# Tiny817_Xplained_Pro_EDBG.net
KiCad netlist of a schematic drawn in Altium Designer
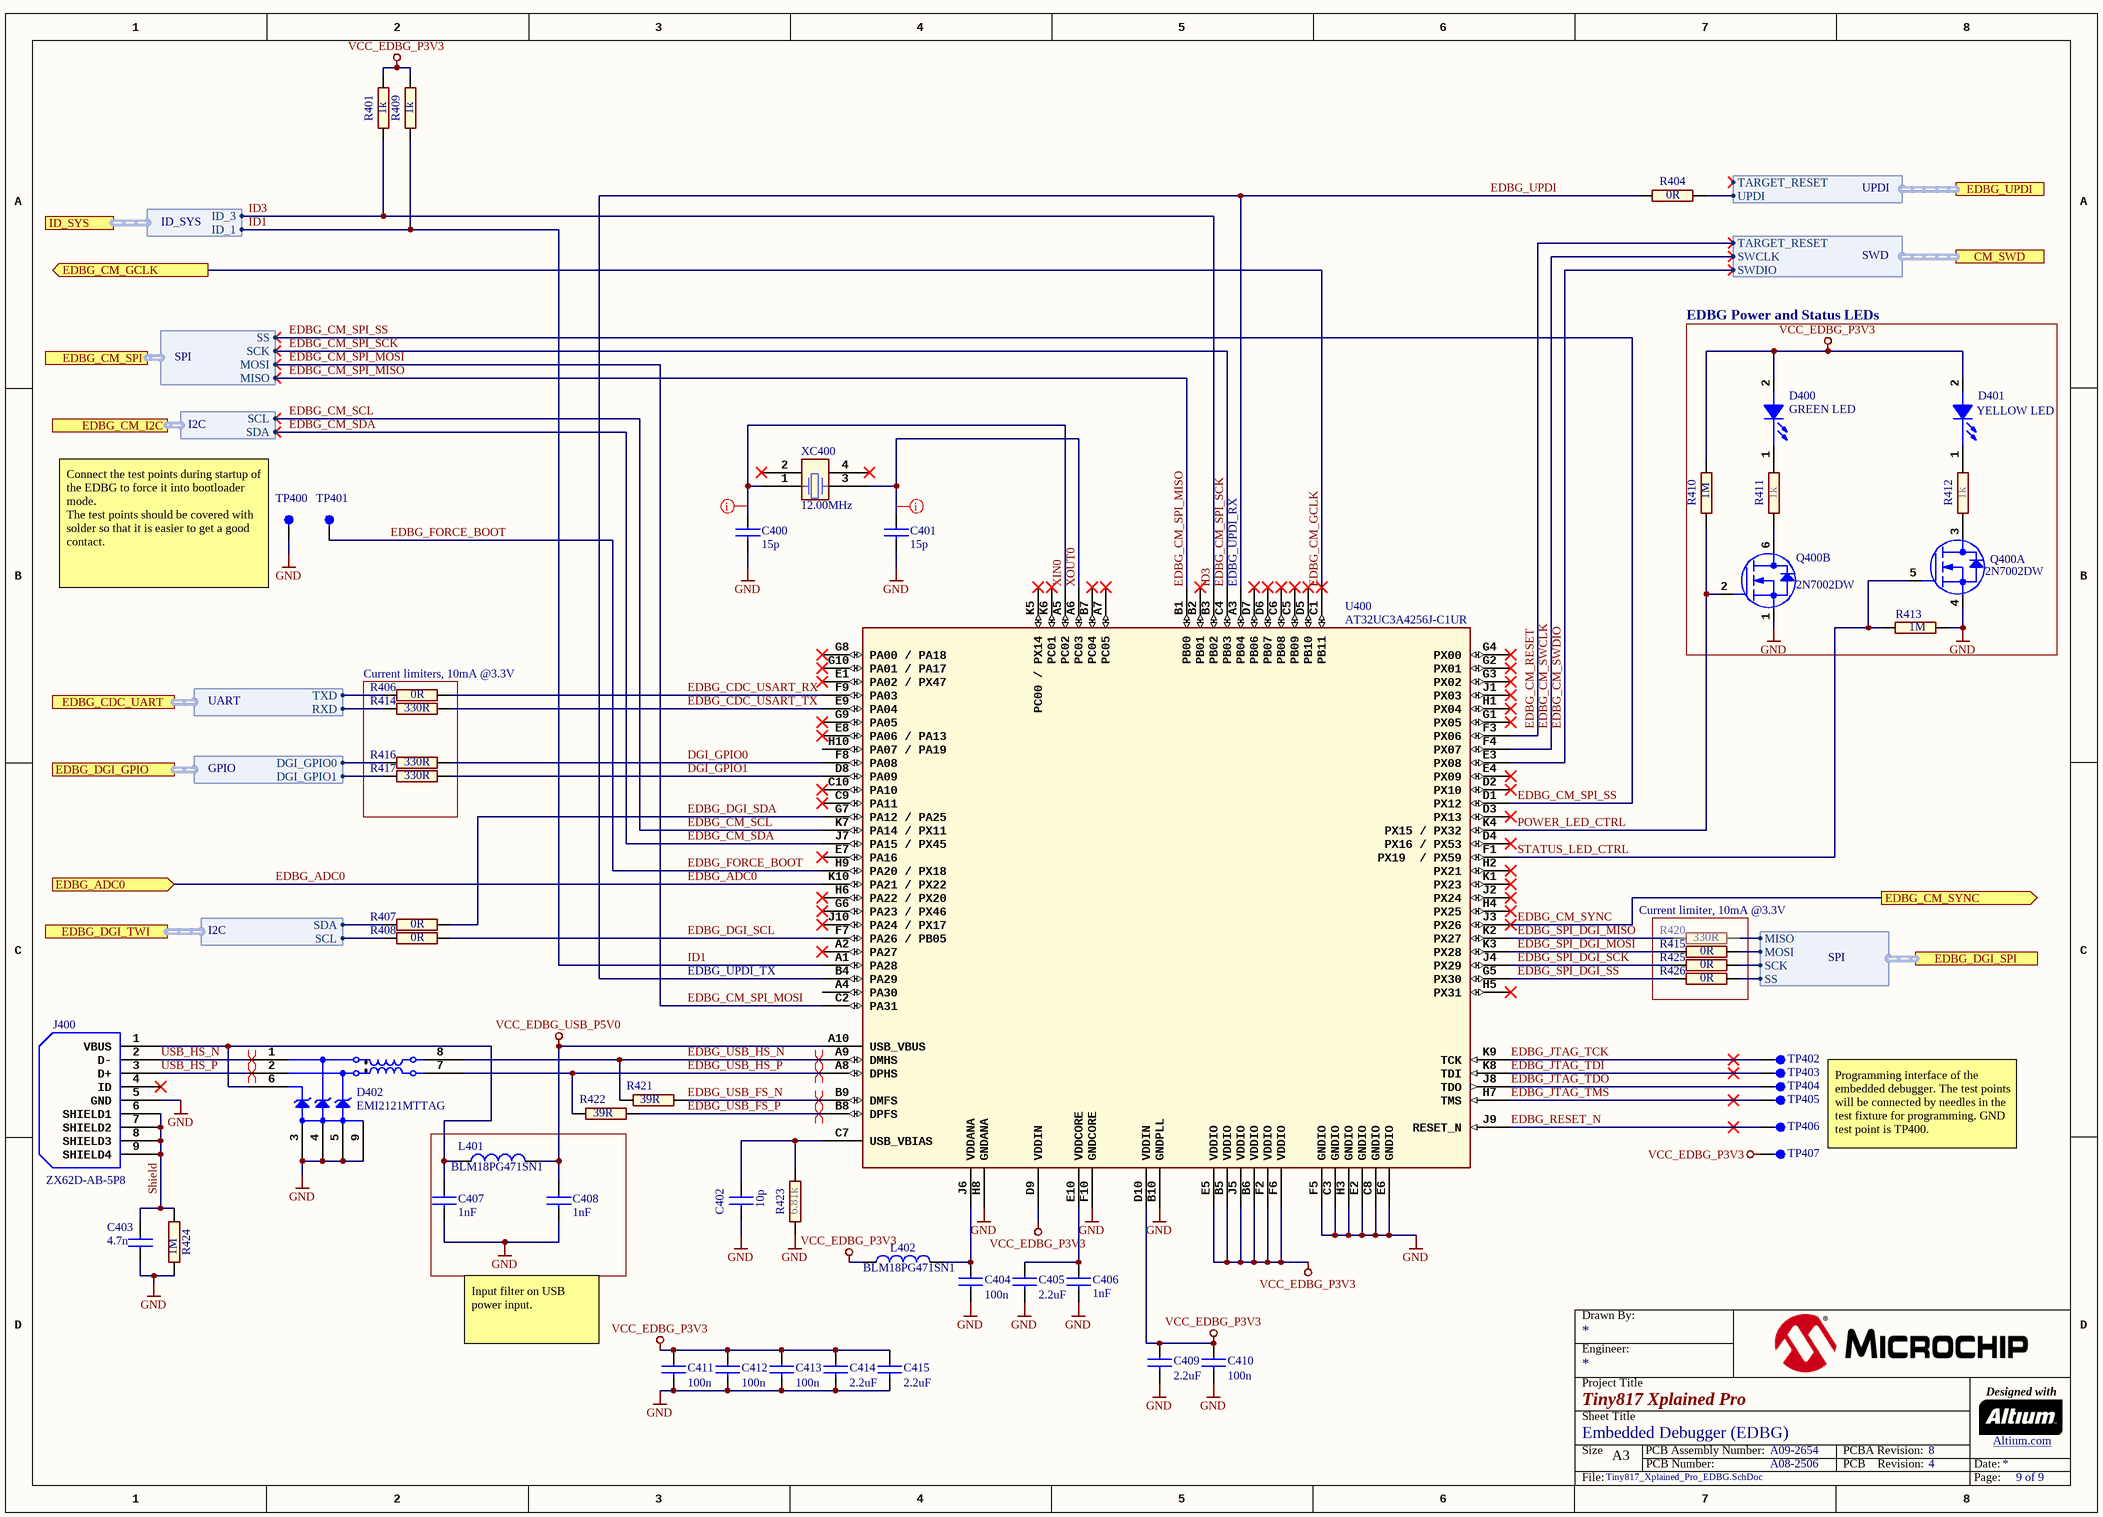
[diagram p0: Tiny817_Xplained_Pro_EDBG.SchDoc]

(export (version "E")
  (design (tool "Eeschema 10.0.6"))
  (components
    (comp (ref "C400")
      (value "15p")
      (footprint "AP1-00053")
      (description "Ceramic capacitor, SMD 0402, NP0, 50V, +/-5%")
      (fields (field (name "TOLERANCE") "50V, +/-5%") (field (name "MANUFACTURER") "AVX"))
      (libsource (lib "AltiumDbLib") (part "CAP-NONPOL"))
    )
    (comp (ref "C401")
      (value "15p")
      (footprint "AP1-00053")
      (description "Ceramic capacitor, SMD 0402, NP0, 50V, +/-5%")
      (fields (field (name "TOLERANCE") "50V, +/-5%") (field (name "MANUFACTURER") "AVX"))
      (libsource (lib "AltiumDbLib") (part "CAP-NONPOL"))
    )
    (comp (ref "C402")
      (value "10p")
      (footprint "AP1-00053")
      (description "Ceramic capacitor, SMD 0402, NP0, 50V, +/-5%")
      (fields (field (name "TOLERANCE") "50V, +/-5%") (field (name "MANUFACTURER") "AVX"))
      (libsource (lib "AltiumDbLib") (part "CAP-NONPOL"))
    )
    (comp (ref "C403")
      (value "4.7n")
      (footprint "AP1-00053")
      (description "Ceramic capacitor, SMD 0402, X7R, 25V, +/-10% (de35287)")
      (fields (field (name "TOLERANCE") "25V, +/-10%") (field (name "MANUFACTURER") "PHYCOMP"))
      (libsource (lib "AltiumDbLib") (part "CAP-NONPOL"))
    )
    (comp (ref "C404")
      (value "100n")
      (footprint "AP1-00053")
      (description "Ceramic capacitor, SMD 0402, X7R, 16V, +/-10%")
      (fields (field (name "TOLERANCE") "16V, +/-10%") (field (name "MANUFACTURER") "Kemet"))
      (libsource (lib "AltiumDbLib") (part "CAP-NONPOL"))
    )
    (comp (ref "C405")
      (value "2.2uF")
      (footprint "AP1-00053")
      (description "Ceramic capacitor, SMD 0402, X5R, 6.3V, +/-20%")
      (fields (field (name "TOLERANCE") "Â±20%") (field (name "MANUFACTURER") "Kemet"))
      (libsource (lib "AltiumDbLib") (part "CAP-NONPOL"))
    )
    (comp (ref "C406")
      (value "1nF")
      (footprint "AP1-00053")
      (description "Ceramic capacitor, SMD 0402, C0G, 50V, +/-5%")
      (fields (field (name "TOLERANCE") "5%") (field (name "MANUFACTURER") "Murata"))
      (libsource (lib "AltiumDbLib") (part "CAP-NONPOL"))
    )
    (comp (ref "C407")
      (value "1nF")
      (footprint "AP1-00053")
      (description "Ceramic capacitor, SMD 0402, C0G, 50V, +/-5%")
      (fields (field (name "TOLERANCE") "5%") (field (name "MANUFACTURER") "Murata"))
      (libsource (lib "AltiumDbLib") (part "CAP-NONPOL"))
    )
    (comp (ref "C408")
      (value "1nF")
      (footprint "AP1-00053")
      (description "Ceramic capacitor, SMD 0402, C0G, 50V, +/-5%")
      (fields (field (name "TOLERANCE") "5%") (field (name "MANUFACTURER") "Murata"))
      (libsource (lib "AltiumDbLib") (part "CAP-NONPOL"))
    )
    (comp (ref "C409")
      (value "2.2uF")
      (footprint "AP1-00053")
      (description "Ceramic capacitor, SMD 0402, X5R, 6.3V, +/-20%")
      (fields (field (name "TOLERANCE") "Â±20%") (field (name "MANUFACTURER") "Kemet"))
      (libsource (lib "AltiumDbLib") (part "CAP-NONPOL"))
    )
    (comp (ref "C410")
      (value "100n")
      (footprint "AP1-00053")
      (description "Ceramic capacitor, SMD 0402, X7R, 16V, +/-10%")
      (fields (field (name "TOLERANCE") "16V, +/-10%") (field (name "MANUFACTURER") "Kemet"))
      (libsource (lib "AltiumDbLib") (part "CAP-NONPOL"))
    )
    (comp (ref "C411")
      (value "100n")
      (footprint "AP1-00053")
      (description "Ceramic capacitor, SMD 0402, X7R, 16V, +/-10%")
      (fields (field (name "TOLERANCE") "16V, +/-10%") (field (name "MANUFACTURER") "Kemet"))
      (libsource (lib "AltiumDbLib") (part "CAP-NONPOL"))
    )
    (comp (ref "C412")
      (value "100n")
      (footprint "AP1-00053")
      (description "Ceramic capacitor, SMD 0402, X7R, 16V, +/-10%")
      (fields (field (name "TOLERANCE") "16V, +/-10%") (field (name "MANUFACTURER") "Kemet"))
      (libsource (lib "AltiumDbLib") (part "CAP-NONPOL"))
    )
    (comp (ref "C413")
      (value "100n")
      (footprint "AP1-00053")
      (description "Ceramic capacitor, SMD 0402, X7R, 16V, +/-10%")
      (fields (field (name "TOLERANCE") "16V, +/-10%") (field (name "MANUFACTURER") "Kemet"))
      (libsource (lib "AltiumDbLib") (part "CAP-NONPOL"))
    )
    (comp (ref "C414")
      (value "2.2uF")
      (footprint "AP1-00053")
      (description "Ceramic capacitor, SMD 0402, X5R, 6.3V, +/-20%")
      (fields (field (name "TOLERANCE") "Â±20%") (field (name "MANUFACTURER") "Kemet"))
      (libsource (lib "AltiumDbLib") (part "CAP-NONPOL"))
    )
    (comp (ref "C415")
      (value "2.2uF")
      (footprint "AP1-00053")
      (description "Ceramic capacitor, SMD 0402, X5R, 6.3V, +/-20%")
      (fields (field (name "TOLERANCE") "Â±20%") (field (name "MANUFACTURER") "Kemet"))
      (libsource (lib "AltiumDbLib") (part "CAP-NONPOL"))
    )
    (comp (ref "D400")
      (value "GREEN LED")
      (footprint "AP4-00160")
      (description "LED, SMD 0402, Green, Wave length=569nm, 2.1mcd @ (1mA, 1.9Vf)rohm")
      (fields (field (name "MANUFACTURER") "ROHM") (field (name "MPN") "SML-P12MTT86R"))
      (libsource (lib "AltiumDbLib") (part "LED_12"))
    )
    (comp (ref "D401")
      (value "YELLOW LED")
      (footprint "AP4-00160")
      (description "LED, SMD 0402, Yellow, Wave length=586nm, 7.6mcd @ (1mA, 1.9Vf)")
      (fields (field (name "MANUFACTURER") "ROHM") (field (name "MPN") "SML-P12YTT86R"))
      (libsource (lib "AltiumDbLib") (part "LED_12"))
    )
    (comp (ref "D402")
      (value "EMI2121MTTAG")
      (footprint "AP4-00159")
      (description "EMI2121, SZEMI2121 Single Pair Common Mode Filter with ESD Protection")
      (fields (field (name "MANUFACTURER") "ON Semiconductor"))
      (libsource (lib "AltiumDbLib") (part "EMI2121"))
    )
    (comp (ref "J400")
      (value "ZX62D-AB-5P8")
      (footprint "AP8-00852")
      (description "Micro USB AB Connector, Standard SMT + DIP")
      (fields (field (name "MANUFACTURER") "Hirose") (field (name "MPN") "ZX62D-AB-5P8(30)"))
      (libsource (lib "AltiumDbLib") (part "USB_AB"))
    )
    (comp (ref "L401")
      (value "BLM18PG471SN1")
      (footprint "AP3-00005")
      (description "SMD RF inductor 0603. Z=470Ohm (@100MHz), Max R(dc)=0.20Ohm, Max current=1A")
      (fields (field (name "MANUFACTURER") "Murata"))
      (libsource (lib "AltiumDbLib") (part "INDUCTOR"))
    )
    (comp (ref "L402")
      (value "BLM18PG471SN1")
      (footprint "AP3-00005")
      (description "SMD RF inductor 0603. Z=470Ohm (@100MHz), Max R(dc)=0.20Ohm, Max current=1A")
      (fields (field (name "MANUFACTURER") "Murata"))
      (libsource (lib "AltiumDbLib") (part "INDUCTOR"))
    )
    (comp (ref "Q400")
      (value "2N7002DW")
      (footprint "AP5-00001")
      (description "Dual N-Channel MOSFET, 60V, 115mA cont,RDS(ON) < 7.5 Ohm @50mA@5V, SOT-363")
      (fields
        (field (name "MANUFACTURER") "Fairchild")
        (field (name "Comment") "Same as 2N7002 but with two MOSFETs in one package")
      )
      (libsource (lib "AltiumDbLib") (part "MOSFET_DUAL_N_S2G2D1S1G1D2"))
    )
    (comp (ref "R401")
      (value "1k")
      (footprint "AP2-00000")
      (description "Thick film resistor, SMD 0402, 1/16W, 1%")
      (fields (field (name "TOLERANCE") "1 %") (field (name "MANUFACTURER") "ASJ Holdings"))
      (libsource (lib "") (part "R2_4"))
    )
    (comp (ref "R404")
      (value "0R")
      (footprint "AP2-00000")
      (description "RES 0.0 OHM 1/16W 0402 SMD")
      (fields (field (name "TOLERANCE") "1 %") (field (name "MANUFACTURER") "(n/a)"))
      (libsource (lib "") (part "R2_3"))
    )
    (comp (ref "R406")
      (value "0R")
      (footprint "AP2-00000")
      (description "RES 0.0 OHM 1/16W 0402 SMD")
      (fields (field (name "TOLERANCE") "1 %") (field (name "MANUFACTURER") "(n/a)"))
      (libsource (lib "") (part "R2_3"))
    )
    (comp (ref "R407")
      (value "0R")
      (footprint "AP2-00000")
      (description "RES 0.0 OHM 1/16W 0402 SMD")
      (fields (field (name "TOLERANCE") "1 %") (field (name "MANUFACTURER") "(n/a)"))
      (libsource (lib "") (part "R2_3"))
    )
    (comp (ref "R408")
      (value "0R")
      (footprint "AP2-00000")
      (description "RES 0.0 OHM 1/16W 0402 SMD")
      (fields (field (name "TOLERANCE") "1 %") (field (name "MANUFACTURER") "(n/a)"))
      (libsource (lib "") (part "R2_3"))
    )
    (comp (ref "R409")
      (value "1k")
      (footprint "AP2-00000")
      (description "Thick film resistor, SMD 0402, 1/16W, 1%")
      (fields (field (name "TOLERANCE") "1 %") (field (name "MANUFACTURER") "ASJ Holdings"))
      (libsource (lib "") (part "R2_4"))
    )
    (comp (ref "R410")
      (value "1M")
      (footprint "AP2-00011")
      (description "Thick film resistor, SMD 0402, 1/16W, 1%")
      (fields (field (name "TOLERANCE") "1 %") (field (name "MANUFACTURER") "ASJ Holdings"))
      (libsource (lib "") (part "R2_4"))
    )
    (comp (ref "R411")
      (value "1k")
      (footprint "AP2-00011")
      (description "Thick film resistor, SMD 0402, 1/16W, 1%")
      (fields (field (name "TOLERANCE") "1 %") (field (name "MANUFACTURER") "ASJ Holdings"))
      (libsource (lib "") (part "R2_4"))
    )
    (comp (ref "R412")
      (value "1k")
      (footprint "AP2-00011")
      (description "Thick film resistor, SMD 0402, 1/16W, 1%")
      (fields (field (name "TOLERANCE") "1 %") (field (name "MANUFACTURER") "ASJ Holdings"))
      (libsource (lib "") (part "R2_4"))
    )
    (comp (ref "R413")
      (value "1M")
      (footprint "AP2-00011")
      (description "Thick film resistor, SMD 0402, 1/16W, 1%")
      (fields (field (name "TOLERANCE") "1 %") (field (name "MANUFACTURER") "ASJ Holdings"))
      (libsource (lib "") (part "R2_3"))
    )
    (comp (ref "R414")
      (value "330R")
      (footprint "AP2-00000")
      (description "Thick film resistor, SMD 0402, 1/16W, 1%")
      (fields (field (name "TOLERANCE") "1 %") (field (name "MANUFACTURER") "ASJ Holdings"))
      (libsource (lib "AltiumDbLib") (part "R2"))
    )
    (comp (ref "R415")
      (value "0R")
      (footprint "AP2-00000")
      (description "RES 0.0 OHM 1/16W 0402 SMD")
      (fields (field (name "TOLERANCE") "1 %") (field (name "MANUFACTURER") "(n/a)"))
      (libsource (lib "") (part "R2_3"))
    )
    (comp (ref "R416")
      (value "330R")
      (footprint "AP2-00000")
      (description "Thick film resistor, SMD 0402, 1/16W, 1%")
      (fields (field (name "TOLERANCE") "1 %") (field (name "MANUFACTURER") "ASJ Holdings"))
      (libsource (lib "AltiumDbLib") (part "R2"))
    )
    (comp (ref "R417")
      (value "330R")
      (footprint "AP2-00000")
      (description "Thick film resistor, SMD 0402, 1/16W, 1%")
      (fields (field (name "TOLERANCE") "1 %") (field (name "MANUFACTURER") "ASJ Holdings"))
      (libsource (lib "AltiumDbLib") (part "R2"))
    )
    (comp (ref "R420")
      (value "330R")
      (footprint "AP2-00000")
      (description "Thick film resistor, SMD 0402, 1/16W, 1%")
      (fields (field (name "TOLERANCE") "1 %") (field (name "MANUFACTURER") "ASJ Holdings"))
      (libsource (lib "AltiumDbLib") (part "R2"))
    )
    (comp (ref "R421")
      (value "39R")
      (footprint "AP2-00011")
      (description "Thick film resistor, SMD 0402, 1/16W, 1%")
      (fields (field (name "TOLERANCE") "1 %") (field (name "MANUFACTURER") "ASJ Holdings"))
      (libsource (lib "") (part "R2_1"))
    )
    (comp (ref "R422")
      (value "39R")
      (footprint "AP2-00011")
      (description "Thick film resistor, SMD 0402, 1/16W, 1%")
      (fields (field (name "TOLERANCE") "1 %") (field (name "MANUFACTURER") "ASJ Holdings"))
      (libsource (lib "") (part "R2_1"))
    )
    (comp (ref "R423")
      (value "6.81k")
      (footprint "AP2-00011")
      (description "Thick film resistor, SMD 0402, 1/16W, 1%")
      (fields (field (name "TOLERANCE") "1%") (field (name "MANUFACTURER") "Vishay"))
      (libsource (lib "") (part "R2_4"))
    )
    (comp (ref "R424")
      (value "1M")
      (footprint "AP2-00011")
      (description "Thick film resistor, SMD 0402, 1/16W, 1%")
      (fields (field (name "TOLERANCE") "1 %") (field (name "MANUFACTURER") "ASJ Holdings"))
      (libsource (lib "") (part "R2_2"))
    )
    (comp (ref "R425")
      (value "0R")
      (footprint "AP2-00000")
      (description "RES 0.0 OHM 1/16W 0402 SMD")
      (fields (field (name "TOLERANCE") "1 %") (field (name "MANUFACTURER") "(n/a)"))
      (libsource (lib "") (part "R2_3"))
    )
    (comp (ref "R426")
      (value "0R")
      (footprint "AP2-00000")
      (description "RES 0.0 OHM 1/16W 0402 SMD")
      (fields (field (name "TOLERANCE") "1 %") (field (name "MANUFACTURER") "(n/a)"))
      (libsource (lib "") (part "R2_3"))
    )
    (comp (ref "TP400")
      (value "~")
      (footprint "AP8-00010")
      (description "Single SMD testpad")
      (libsource (lib "AltiumDbLib") (part "TESTPOINT"))
    )
    (comp (ref "TP401")
      (value "~")
      (footprint "AP8-00010")
      (description "Single SMD testpad")
      (libsource (lib "AltiumDbLib") (part "TESTPOINT"))
    )
    (comp (ref "TP402")
      (value "~")
      (footprint "AP8-00010")
      (description "Single SMD testpad")
      (libsource (lib "AltiumDbLib") (part "TESTPOINT"))
    )
    (comp (ref "TP403")
      (value "~")
      (footprint "AP8-00010")
      (description "Single SMD testpad")
      (libsource (lib "AltiumDbLib") (part "TESTPOINT"))
    )
    (comp (ref "TP404")
      (value "~")
      (footprint "AP8-00010")
      (description "Single SMD testpad")
      (libsource (lib "AltiumDbLib") (part "TESTPOINT"))
    )
    (comp (ref "TP405")
      (value "~")
      (footprint "AP8-00010")
      (description "Single SMD testpad")
      (libsource (lib "AltiumDbLib") (part "TESTPOINT"))
    )
    (comp (ref "TP406")
      (value "~")
      (footprint "AP8-00010")
      (description "Single SMD testpad")
      (libsource (lib "AltiumDbLib") (part "TESTPOINT"))
    )
    (comp (ref "TP407")
      (value "~")
      (footprint "AP8-00010")
      (description "Single SMD testpad")
      (libsource (lib "AltiumDbLib") (part "TESTPOINT"))
    )
    (comp (ref "U400")
      (value "AT32UC3A4256J-C1UR")
      (footprint "AP6-00206")
      (description "EDBG controller")
      (fields (field (name "MANUFACTURER") "Microchip") (field (name "Comment") "100 ball VFBGA"))
      (libsource (lib "AltiumDbLib") (part "AT32UC3A4_VFBGA"))
    )
    (comp (ref "XC400")
      (value "12.00MHz")
      (footprint "AP7-00089")
      (description "Kyocera CX3225GB12000H0KPSC1, 12MHz, 12pF, SMD crystal")
      (fields
        (field (name "TOLERANCE") "Â±30ppm")
        (field (name "MANUFACTURER") "Kyocera Crystal Device Corporation")
      )
      (libsource (lib "AltiumDbLib") (part "CRYSTAL1324"))
    )
  )
  (nets
    (net (code "7") (name "/DGI_GPIO0") (class "Default")
      (node (ref "R416") (pin "2") (pinfunction "2_2") (pintype "passive"))
      (node (ref "U400") (pin "F8") (pinfunction "PA08_F8") (pintype "bidirectional"))
    )
    (net (code "8") (name "/DGI_GPIO1") (class "Default")
      (node (ref "R417") (pin "2") (pinfunction "2_2") (pintype "passive"))
      (node (ref "U400") (pin "D8") (pinfunction "PA09_D8") (pintype "bidirectional"))
    )
    (net (code "9") (name "/EDBG_ADC0") (class "Default")
      (node (ref "U400") (pin "K10") (pinfunction "PA21_/_PX22_K10") (pintype "bidirectional"))
    )
    (net (code "10") (name "/EDBG_CDC_USART_RX") (class "Default")
      (node (ref "R406") (pin "1") (pinfunction "1_1") (pintype "passive"))
      (node (ref "U400") (pin "F9") (pinfunction "PA03_F9") (pintype "bidirectional"))
    )
    (net (code "11") (name "/EDBG_CDC_USART_TX") (class "Default")
      (node (ref "R414") (pin "2") (pinfunction "2_2") (pintype "passive"))
      (node (ref "U400") (pin "E9") (pinfunction "PA04_E9") (pintype "bidirectional"))
    )
    (net (code "12") (name "/EDBG_CM_GCLK") (class "Default")
      (node (ref "U400") (pin "C1") (pinfunction "PB11_C1") (pintype "bidirectional+no_connect"))
    )
    (net (code "13") (name "/EDBG_CM_RESET") (class "Default")
      (node (ref "U400") (pin "F3") (pinfunction "PX06_F3") (pintype "bidirectional+no_connect"))
    )
    (net (code "14") (name "/EDBG_CM_SCL") (class "Default")
      (node (ref "U400") (pin "K7") (pinfunction "PA14_/_PX11_K7") (pintype "bidirectional+no_connect"))
    )
    (net (code "15") (name "/EDBG_CM_SDA") (class "Default")
      (node (ref "U400") (pin "J7") (pinfunction "PA15_/_PX45_J7") (pintype "bidirectional+no_connect"))
    )
    (net (code "16") (name "/EDBG_CM_SPI_MISO") (class "Default")
      (node (ref "U400") (pin "B1") (pinfunction "PB00_B1") (pintype "bidirectional+no_connect"))
    )
    (net (code "17") (name "/EDBG_CM_SPI_MOSI") (class "Default")
      (node (ref "U400") (pin "C2") (pinfunction "PA31_C2") (pintype "bidirectional+no_connect"))
    )
    (net (code "18") (name "/EDBG_CM_SPI_SCK") (class "Default")
      (node (ref "U400") (pin "C4") (pinfunction "PB03_C4") (pintype "bidirectional+no_connect"))
    )
    (net (code "19") (name "/EDBG_CM_SPI_SS") (class "Default")
      (node (ref "U400") (pin "D1") (pinfunction "PX12_D1") (pintype "bidirectional+no_connect"))
    )
    (net (code "20") (name "/EDBG_CM_SWCLK") (class "Default")
      (node (ref "U400") (pin "F4") (pinfunction "PX07_F4") (pintype "bidirectional+no_connect"))
    )
    (net (code "21") (name "/EDBG_CM_SWDIO") (class "Default")
      (node (ref "U400") (pin "E3") (pinfunction "PX08_E3") (pintype "bidirectional+no_connect"))
    )
    (net (code "22") (name "/EDBG_CM_SYNC") (class "Default")
      (node (ref "U400") (pin "J3") (pinfunction "PX26_J3") (pintype "bidirectional+no_connect"))
    )
    (net (code "23") (name "/EDBG_DGI_SCL") (class "Default")
      (node (ref "R408") (pin "1") (pinfunction "1_1") (pintype "passive"))
      (node (ref "U400") (pin "F7") (pinfunction "PA26_/_PB05_F7") (pintype "bidirectional"))
    )
    (net (code "24") (name "/EDBG_DGI_SDA") (class "Default")
      (node (ref "R407") (pin "1") (pinfunction "1_1") (pintype "passive"))
      (node (ref "U400") (pin "G7") (pinfunction "PA12_/_PA25_G7") (pintype "bidirectional"))
    )
    (net (code "25") (name "/EDBG_FORCE_BOOT") (class "Default")
      (node (ref "TP401") (pin "1") (pinfunction "1_1") (pintype "passive"))
      (node (ref "U400") (pin "H9") (pinfunction "PA20_/_PX18_H9") (pintype "bidirectional"))
    )
    (net (code "26") (name "/EDBG_JTAG_TCK") (class "Default")
      (node (ref "TP402") (pin "1") (pinfunction "1_1") (pintype "passive"))
      (node (ref "U400") (pin "K9") (pinfunction "TCK_K9") (pintype "input"))
    )
    (net (code "27") (name "/EDBG_JTAG_TDI") (class "Default")
      (node (ref "TP403") (pin "1") (pinfunction "1_1") (pintype "passive"))
      (node (ref "U400") (pin "K8") (pinfunction "TDI_K8") (pintype "input"))
    )
    (net (code "28") (name "/EDBG_JTAG_TDO") (class "Default")
      (node (ref "TP404") (pin "1") (pinfunction "1_1") (pintype "passive"))
      (node (ref "U400") (pin "J8") (pinfunction "TDO_J8") (pintype "output"))
    )
    (net (code "29") (name "/EDBG_JTAG_TMS") (class "Default")
      (node (ref "TP405") (pin "1") (pinfunction "1_1") (pintype "passive"))
      (node (ref "U400") (pin "H7") (pinfunction "TMS_H7") (pintype "input"))
    )
    (net (code "30") (name "/EDBG_RESET_N") (class "Default")
      (node (ref "TP406") (pin "1") (pinfunction "1_1") (pintype "passive"))
      (node (ref "U400") (pin "J9") (pinfunction "RESET_N_J9") (pintype "input"))
    )
    (net (code "31") (name "/EDBG_SPI_DGI_MISO") (class "Default")
      (node (ref "R420") (pin "1") (pinfunction "1_1") (pintype "passive"))
      (node (ref "U400") (pin "K2") (pinfunction "PX27_K2") (pintype "bidirectional"))
    )
    (net (code "32") (name "/EDBG_SPI_DGI_MOSI") (class "Default")
      (node (ref "R415") (pin "2") (pinfunction "2_2") (pintype "passive"))
      (node (ref "U400") (pin "K3") (pinfunction "PX28_K3") (pintype "bidirectional"))
    )
    (net (code "33") (name "/EDBG_SPI_DGI_SCK") (class "Default")
      (node (ref "R425") (pin "2") (pinfunction "2_2") (pintype "passive"))
      (node (ref "U400") (pin "J4") (pinfunction "PX29_J4") (pintype "bidirectional"))
    )
    (net (code "34") (name "/EDBG_SPI_DGI_SS") (class "Default")
      (node (ref "R426") (pin "2") (pinfunction "2_2") (pintype "passive"))
      (node (ref "U400") (pin "G5") (pinfunction "PX30_G5") (pintype "bidirectional"))
    )
    (net (code "35") (name "/EDBG_UPDI") (class "Default")
      (node (ref "R404") (pin "2") (pinfunction "2_2") (pintype "passive"))
      (node (ref "U400") (pin "A3") (pinfunction "PB04_A3") (pintype "bidirectional"))
      (node (ref "U400") (pin "B4") (pinfunction "PA29_B4") (pintype "bidirectional"))
    )
    (net (code "36") (name "/EDBG_USB_FS_N") (class "Default")
      (node (ref "R421") (pin "2") (pinfunction "2_2") (pintype "passive"))
      (node (ref "U400") (pin "B9") (pinfunction "DMFS_B9") (pintype "bidirectional"))
    )
    (net (code "37") (name "/EDBG_USB_FS_P") (class "Default")
      (node (ref "R422") (pin "2") (pinfunction "2_2") (pintype "passive"))
      (node (ref "U400") (pin "B8") (pinfunction "DPFS_B8") (pintype "bidirectional"))
    )
    (net (code "38") (name "/EDBG_USB_HS_N") (class "Default")
      (node (ref "D402") (pin "8") (pinfunction "DIFF1_INT_8") (pintype "passive"))
      (node (ref "R421") (pin "1") (pinfunction "1_1") (pintype "passive"))
      (node (ref "U400") (pin "A9") (pinfunction "DMHS_A9") (pintype "bidirectional"))
    )
    (net (code "39") (name "/EDBG_USB_HS_P") (class "Default")
      (node (ref "D402") (pin "7") (pinfunction "DIFF2_INT_7") (pintype "passive"))
      (node (ref "R422") (pin "1") (pinfunction "1_1") (pintype "passive"))
      (node (ref "U400") (pin "A8") (pinfunction "DPHS_A8") (pintype "bidirectional"))
    )
    (net (code "40") (name "/ID1") (class "Default")
      (node (ref "R409") (pin "1") (pinfunction "1_1") (pintype "passive"))
      (node (ref "U400") (pin "A1") (pinfunction "PA28_A1") (pintype "bidirectional"))
    )
    (net (code "41") (name "/ID3") (class "Default")
      (node (ref "R401") (pin "1") (pinfunction "1_1") (pintype "passive"))
      (node (ref "U400") (pin "B3") (pinfunction "PB02_B3") (pintype "bidirectional"))
    )
    (net (code "42") (name "/POWER_LED_CTRL") (class "Default")
      (node (ref "Q400") (pin "2") (pinfunction "G2_2") (pintype "passive"))
      (node (ref "R410") (pin "1") (pinfunction "1_1") (pintype "passive"))
      (node (ref "U400") (pin "K4") (pinfunction "PX15_/_PX32_K4") (pintype "bidirectional"))
    )
    (net (code "43") (name "/RXD") (class "Default")
      (node (ref "R414") (pin "1") (pinfunction "1_1") (pintype "passive"))
    )
    (net (code "44") (name "/STATUS_LED_CTRL") (class "Default")
      (node (ref "Q400") (pin "5") (pinfunction "G1_5") (pintype "passive"))
      (node (ref "R413") (pin "2") (pinfunction "2_2") (pintype "passive"))
      (node (ref "U400") (pin "F1") (pinfunction "PX19__/_PX59_F1") (pintype "bidirectional"))
    )
    (net (code "45") (name "/Shield") (class "Default")
      (node (ref "C403") (pin "2") (pinfunction "2_2") (pintype "passive"))
      (node (ref "J400") (pin "6") (pinfunction "SHIELD1_6") (pintype "passive"))
      (node (ref "J400") (pin "7") (pinfunction "SHIELD2_7") (pintype "passive"))
      (node (ref "J400") (pin "8") (pinfunction "SHIELD3_8") (pintype "passive"))
      (node (ref "J400") (pin "9") (pinfunction "SHIELD4_9") (pintype "passive"))
      (node (ref "R424") (pin "2") (pinfunction "2_2") (pintype "passive"))
    )
    (net (code "46") (name "/TXD") (class "Default")
      (node (ref "R406") (pin "2") (pinfunction "2_2") (pintype "passive"))
    )
    (net (code "47") (name "/UPDI") (class "Default")
      (node (ref "R404") (pin "1") (pinfunction "1_1") (pintype "passive"))
    )
    (net (code "48") (name "/USB_HS_N") (class "Default")
      (node (ref "D402") (pin "1") (pinfunction "DIFF1_EXT_1") (pintype "passive"))
      (node (ref "J400") (pin "2") (pinfunction "D-_2") (pintype "passive"))
    )
    (net (code "49") (name "/USB_HS_P") (class "Default")
      (node (ref "D402") (pin "2") (pinfunction "DIFF2_EXT_2") (pintype "passive"))
      (node (ref "J400") (pin "3") (pinfunction "D+_3") (pintype "passive"))
    )
    (net (code "50") (name "/XIN0") (class "Default")
      (node (ref "C400") (pin "1") (pinfunction "1_1") (pintype "passive"))
      (node (ref "U400") (pin "A5") (pinfunction "PC02_A5") (pintype "bidirectional"))
      (node (ref "XC400") (pin "1") (pinfunction "1_1") (pintype "passive"))
    )
    (net (code "51") (name "/XOUT0") (class "Default")
      (node (ref "C401") (pin "1") (pinfunction "1_1") (pintype "passive"))
      (node (ref "U400") (pin "A6") (pinfunction "PC03_A6") (pintype "bidirectional"))
      (node (ref "XC400") (pin "3") (pinfunction "3_3") (pintype "passive"))
    )
    (net (code "59") (name "GND") (class "Default")
      (node (ref "C400") (pin "2") (pinfunction "2_2") (pintype "passive"))
      (node (ref "C401") (pin "2") (pinfunction "2_2") (pintype "passive"))
      (node (ref "C402") (pin "2") (pinfunction "2_2") (pintype "passive"))
      (node (ref "C403") (pin "1") (pinfunction "1_1") (pintype "passive"))
      (node (ref "C404") (pin "2") (pinfunction "2_2") (pintype "passive"))
      (node (ref "C405") (pin "2") (pinfunction "2_2") (pintype "passive"))
      (node (ref "C406") (pin "2") (pinfunction "2_2") (pintype "passive"))
      (node (ref "C407") (pin "2") (pinfunction "2_2") (pintype "passive"))
      (node (ref "C408") (pin "2") (pinfunction "2_2") (pintype "passive"))
      (node (ref "C409") (pin "2") (pinfunction "2_2") (pintype "passive"))
      (node (ref "C410") (pin "2") (pinfunction "2_2") (pintype "passive"))
      (node (ref "C411") (pin "2") (pinfunction "2_2") (pintype "passive"))
      (node (ref "C412") (pin "2") (pinfunction "2_2") (pintype "passive"))
      (node (ref "C413") (pin "2") (pinfunction "2_2") (pintype "passive"))
      (node (ref "C414") (pin "2") (pinfunction "2_2") (pintype "passive"))
      (node (ref "C415") (pin "2") (pinfunction "2_2") (pintype "passive"))
      (node (ref "D402") (pin "3") (pinfunction "GND_3") (pintype "power_in"))
      (node (ref "D402") (pin "4") (pinfunction "GND_4") (pintype "power_in"))
      (node (ref "D402") (pin "5") (pinfunction "GND_5") (pintype "power_in"))
      (node (ref "D402") (pin "9") (pinfunction "GND_9") (pintype "power_in"))
      (node (ref "J400") (pin "5") (pinfunction "GND_5") (pintype "passive"))
      (node (ref "Q400") (pin "1") (pinfunction "S2_1") (pintype "passive"))
      (node (ref "Q400") (pin "4") (pinfunction "S1_4") (pintype "passive"))
      (node (ref "R413") (pin "1") (pinfunction "1_1") (pintype "passive"))
      (node (ref "R423") (pin "1") (pinfunction "1_1") (pintype "passive"))
      (node (ref "R424") (pin "1") (pinfunction "1_1") (pintype "passive"))
      (node (ref "TP400") (pin "1") (pinfunction "1_1") (pintype "passive"))
      (node (ref "U400") (pin "B10") (pinfunction "GNDPLL_B10") (pintype "power_in"))
      (node (ref "U400") (pin "C3") (pinfunction "GNDIO_C3") (pintype "power_in"))
      (node (ref "U400") (pin "C8") (pinfunction "GNDIO_C8") (pintype "power_in"))
      (node (ref "U400") (pin "E2") (pinfunction "GNDIO_E2") (pintype "power_in"))
      (node (ref "U400") (pin "E6") (pinfunction "GNDIO_E6") (pintype "power_in"))
      (node (ref "U400") (pin "F10") (pinfunction "GNDCORE_F10") (pintype "power_in"))
      (node (ref "U400") (pin "F5") (pinfunction "GNDIO_F5") (pintype "power_in"))
      (node (ref "U400") (pin "H3") (pinfunction "GNDIO_H3") (pintype "power_in"))
      (node (ref "U400") (pin "H8") (pinfunction "GNDANA_H8") (pintype "power_in"))
    )
    (net (code "60") (name "Net-(D400-CATHODE)") (class "Default")
      (node (ref "D400") (pin "1") (pinfunction "CATHODE_1") (pintype "passive"))
      (node (ref "R411") (pin "2") (pinfunction "2_2") (pintype "passive"))
    )
    (net (code "61") (name "Net-(D401-CATHODE)") (class "Default")
      (node (ref "D401") (pin "1") (pinfunction "CATHODE_1") (pintype "passive"))
      (node (ref "R412") (pin "2") (pinfunction "2_2") (pintype "passive"))
    )
    (net (code "62") (name "Net-(D402-VBUS)") (class "Default")
      (node (ref "C407") (pin "1") (pinfunction "1_1") (pintype "passive"))
      (node (ref "D402") (pin "6") (pinfunction "VBUS_6") (pintype "passive"))
      (node (ref "J400") (pin "1") (pinfunction "VBUS_1") (pintype "passive"))
      (node (ref "L401") (pin "1") (pinfunction "1_1") (pintype "passive"))
    )
    (net (code "63") (name "Net-(Q400A-D1)") (class "Default")
      (node (ref "Q400") (pin "3") (pinfunction "D1_3") (pintype "passive"))
      (node (ref "R412") (pin "1") (pinfunction "1_1") (pintype "passive"))
    )
    (net (code "64") (name "Net-(Q400B-D2)") (class "Default")
      (node (ref "Q400") (pin "6") (pinfunction "D2_6") (pintype "passive"))
      (node (ref "R411") (pin "1") (pinfunction "1_1") (pintype "passive"))
    )
    (net (code "65") (name "Net-(U400-USB_VBIAS)") (class "Default")
      (node (ref "C402") (pin "1") (pinfunction "1_1") (pintype "passive"))
      (node (ref "R423") (pin "2") (pinfunction "2_2") (pintype "passive"))
      (node (ref "U400") (pin "C7") (pinfunction "USB_VBIAS_C7") (pintype "power_in"))
    )
    (net (code "66") (name "Net-(U400-VDDANA)") (class "Default")
      (node (ref "C404") (pin "1") (pinfunction "1_1") (pintype "passive"))
      (node (ref "L402") (pin "2") (pinfunction "2_2") (pintype "passive"))
      (node (ref "U400") (pin "J6") (pinfunction "VDDANA_J6") (pintype "power_in"))
    )
    (net (code "67") (name "Net-(U400-VDDCORE)") (class "Default")
      (node (ref "C405") (pin "1") (pinfunction "1_1") (pintype "passive"))
      (node (ref "C406") (pin "1") (pinfunction "1_1") (pintype "passive"))
      (node (ref "U400") (pin "E10") (pinfunction "VDDCORE_E10") (pintype "power_in"))
    )
    (net (code "68") (name "VCC_EDBG_P3V3") (class "Default")
      (node (ref "C409") (pin "1") (pinfunction "1_1") (pintype "passive"))
      (node (ref "C410") (pin "1") (pinfunction "1_1") (pintype "passive"))
      (node (ref "C411") (pin "1") (pinfunction "1_1") (pintype "passive"))
      (node (ref "C412") (pin "1") (pinfunction "1_1") (pintype "passive"))
      (node (ref "C413") (pin "1") (pinfunction "1_1") (pintype "passive"))
      (node (ref "C414") (pin "1") (pinfunction "1_1") (pintype "passive"))
      (node (ref "C415") (pin "1") (pinfunction "1_1") (pintype "passive"))
      (node (ref "D400") (pin "2") (pinfunction "ANODE_2") (pintype "passive"))
      (node (ref "D401") (pin "2") (pinfunction "ANODE_2") (pintype "passive"))
      (node (ref "L402") (pin "1") (pinfunction "1_1") (pintype "passive"))
      (node (ref "R401") (pin "2") (pinfunction "2_2") (pintype "passive"))
      (node (ref "R409") (pin "2") (pinfunction "2_2") (pintype "passive"))
      (node (ref "R410") (pin "2") (pinfunction "2_2") (pintype "passive"))
      (node (ref "TP407") (pin "1") (pinfunction "1_1") (pintype "passive"))
      (node (ref "U400") (pin "B5") (pinfunction "VDDIO_B5") (pintype "power_in"))
      (node (ref "U400") (pin "B6") (pinfunction "VDDIO_B6") (pintype "power_in"))
      (node (ref "U400") (pin "D10") (pinfunction "VDDIN_D10") (pintype "power_in"))
      (node (ref "U400") (pin "D9") (pinfunction "VDDIN_D9") (pintype "power_in"))
      (node (ref "U400") (pin "E5") (pinfunction "VDDIO_E5") (pintype "power_in"))
      (node (ref "U400") (pin "F2") (pinfunction "VDDIO_F2") (pintype "power_in"))
      (node (ref "U400") (pin "F6") (pinfunction "VDDIO_F6") (pintype "power_in"))
      (node (ref "U400") (pin "J5") (pinfunction "VDDIO_J5") (pintype "power_in"))
    )
    (net (code "69") (name "VCC_EDBG_USB_P5V0") (class "Default")
      (node (ref "C408") (pin "1") (pinfunction "1_1") (pintype "passive"))
      (node (ref "L401") (pin "2") (pinfunction "2_2") (pintype "passive"))
      (node (ref "U400") (pin "A10") (pinfunction "USB_VBUS_A10") (pintype "power_in"))
    )
    (net (code "70") (name "unconnected-(J400-ID-Pad4)") (class "Default")
      (node (ref "J400") (pin "4") (pinfunction "ID_4") (pintype "passive+no_connect"))
    )
    (net (code "71") (name "unconnected-(R407-Pad2)") (class "Default")
      (node (ref "R407") (pin "2") (pinfunction "2_2") (pintype "passive"))
    )
    (net (code "72") (name "unconnected-(R408-Pad2)") (class "Default")
      (node (ref "R408") (pin "2") (pinfunction "2_2") (pintype "passive"))
    )
    (net (code "73") (name "unconnected-(R415-Pad1)") (class "Default")
      (node (ref "R415") (pin "1") (pinfunction "1_1") (pintype "passive"))
    )
    (net (code "74") (name "unconnected-(R416-Pad1)") (class "Default")
      (node (ref "R416") (pin "1") (pinfunction "1_1") (pintype "passive"))
    )
    (net (code "75") (name "unconnected-(R417-Pad1)") (class "Default")
      (node (ref "R417") (pin "1") (pinfunction "1_1") (pintype "passive"))
    )
    (net (code "76") (name "unconnected-(R420-Pad2)") (class "Default")
      (node (ref "R420") (pin "2") (pinfunction "2_2") (pintype "passive"))
    )
    (net (code "77") (name "unconnected-(R425-Pad1)") (class "Default")
      (node (ref "R425") (pin "1") (pinfunction "1_1") (pintype "passive"))
    )
    (net (code "78") (name "unconnected-(R426-Pad1)") (class "Default")
      (node (ref "R426") (pin "1") (pinfunction "1_1") (pintype "passive"))
    )
    (net (code "79") (name "unconnected-(U400-PA00_{slash}_PA18-PadG8)") (class "Default")
      (node (ref "U400") (pin "G8") (pinfunction "PA00_/_PA18_G8") (pintype "bidirectional+no_connect"))
    )
    (net (code "80") (name "unconnected-(U400-PA01_{slash}_PA17-PadG10)") (class "Default")
      (node (ref "U400") (pin "G10") (pinfunction "PA01_/_PA17_G10") (pintype "bidirectional+no_connect"))
    )
    (net (code "81") (name "unconnected-(U400-PA02_{slash}_PX47-PadE1)") (class "Default")
      (node (ref "U400") (pin "E1") (pinfunction "PA02_/_PX47_E1") (pintype "bidirectional+no_connect"))
    )
    (net (code "82") (name "unconnected-(U400-PA05-PadG9)") (class "Default")
      (node (ref "U400") (pin "G9") (pinfunction "PA05_G9") (pintype "bidirectional+no_connect"))
    )
    (net (code "83") (name "unconnected-(U400-PA06_{slash}_PA13-PadE8)") (class "Default")
      (node (ref "U400") (pin "E8") (pinfunction "PA06_/_PA13_E8") (pintype "bidirectional+no_connect"))
    )
    (net (code "84") (name "unconnected-(U400-PA07_{slash}_PA19-PadH10)") (class "Default")
      (node (ref "U400") (pin "H10") (pinfunction "PA07_/_PA19_H10") (pintype "bidirectional"))
    )
    (net (code "85") (name "unconnected-(U400-PA10-PadC10)") (class "Default")
      (node (ref "U400") (pin "C10") (pinfunction "PA10_C10") (pintype "bidirectional+no_connect"))
    )
    (net (code "86") (name "unconnected-(U400-PA11-PadC9)") (class "Default")
      (node (ref "U400") (pin "C9") (pinfunction "PA11_C9") (pintype "bidirectional+no_connect"))
    )
    (net (code "87") (name "unconnected-(U400-PA16-PadE7)") (class "Default")
      (node (ref "U400") (pin "E7") (pinfunction "PA16_E7") (pintype "bidirectional+no_connect"))
    )
    (net (code "88") (name "unconnected-(U400-PA22_{slash}_PX20-PadH6)") (class "Default")
      (node (ref "U400") (pin "H6") (pinfunction "PA22_/_PX20_H6") (pintype "bidirectional+no_connect"))
    )
    (net (code "89") (name "unconnected-(U400-PA23_{slash}_PX46-PadG6)") (class "Default")
      (node (ref "U400") (pin "G6") (pinfunction "PA23_/_PX46_G6") (pintype "bidirectional+no_connect"))
    )
    (net (code "90") (name "unconnected-(U400-PA24_{slash}_PX17-PadJ10)") (class "Default")
      (node (ref "U400") (pin "J10") (pinfunction "PA24_/_PX17_J10") (pintype "bidirectional+no_connect"))
    )
    (net (code "91") (name "unconnected-(U400-PA27-PadA2)") (class "Default")
      (node (ref "U400") (pin "A2") (pinfunction "PA27_A2") (pintype "bidirectional+no_connect"))
    )
    (net (code "92") (name "unconnected-(U400-PA30-PadA4)") (class "Default")
      (node (ref "U400") (pin "A4") (pinfunction "PA30_A4") (pintype "bidirectional"))
    )
    (net (code "93") (name "unconnected-(U400-PB01-PadB2)") (class "Default")
      (node (ref "U400") (pin "B2") (pinfunction "PB01_B2") (pintype "bidirectional+no_connect"))
    )
    (net (code "94") (name "unconnected-(U400-PB06-PadD7)") (class "Default")
      (node (ref "U400") (pin "D7") (pinfunction "PB06_D7") (pintype "bidirectional+no_connect"))
    )
    (net (code "95") (name "unconnected-(U400-PB07-PadD6)") (class "Default")
      (node (ref "U400") (pin "D6") (pinfunction "PB07_D6") (pintype "bidirectional+no_connect"))
    )
    (net (code "96") (name "unconnected-(U400-PB08-PadC6)") (class "Default")
      (node (ref "U400") (pin "C6") (pinfunction "PB08_C6") (pintype "bidirectional+no_connect"))
    )
    (net (code "97") (name "unconnected-(U400-PB09-PadC5)") (class "Default")
      (node (ref "U400") (pin "C5") (pinfunction "PB09_C5") (pintype "bidirectional+no_connect"))
    )
    (net (code "98") (name "unconnected-(U400-PB10-PadD5)") (class "Default")
      (node (ref "U400") (pin "D5") (pinfunction "PB10_D5") (pintype "bidirectional+no_connect"))
    )
    (net (code "99") (name "unconnected-(U400-PC00_{slash}_PX14-PadK5)") (class "Default")
      (node (ref "U400") (pin "K5") (pinfunction "PC00_/_PX14_K5") (pintype "bidirectional+no_connect"))
    )
    (net (code "100") (name "unconnected-(U400-PC01-PadK6)") (class "Default")
      (node (ref "U400") (pin "K6") (pinfunction "PC01_K6") (pintype "bidirectional+no_connect"))
    )
    (net (code "101") (name "unconnected-(U400-PC04-PadB7)") (class "Default")
      (node (ref "U400") (pin "B7") (pinfunction "PC04_B7") (pintype "bidirectional+no_connect"))
    )
    (net (code "102") (name "unconnected-(U400-PC05-PadA7)") (class "Default")
      (node (ref "U400") (pin "A7") (pinfunction "PC05_A7") (pintype "bidirectional+no_connect"))
    )
    (net (code "103") (name "unconnected-(U400-PX00-PadG4)") (class "Default")
      (node (ref "U400") (pin "G4") (pinfunction "PX00_G4") (pintype "bidirectional+no_connect"))
    )
    (net (code "104") (name "unconnected-(U400-PX01-PadG2)") (class "Default")
      (node (ref "U400") (pin "G2") (pinfunction "PX01_G2") (pintype "bidirectional+no_connect"))
    )
    (net (code "105") (name "unconnected-(U400-PX02-PadG3)") (class "Default")
      (node (ref "U400") (pin "G3") (pinfunction "PX02_G3") (pintype "bidirectional+no_connect"))
    )
    (net (code "106") (name "unconnected-(U400-PX03-PadJ1)") (class "Default")
      (node (ref "U400") (pin "J1") (pinfunction "PX03_J1") (pintype "bidirectional+no_connect"))
    )
    (net (code "107") (name "unconnected-(U400-PX04-PadH1)") (class "Default")
      (node (ref "U400") (pin "H1") (pinfunction "PX04_H1") (pintype "bidirectional+no_connect"))
    )
    (net (code "108") (name "unconnected-(U400-PX05-PadG1)") (class "Default")
      (node (ref "U400") (pin "G1") (pinfunction "PX05_G1") (pintype "bidirectional+no_connect"))
    )
    (net (code "109") (name "unconnected-(U400-PX09-PadE4)") (class "Default")
      (node (ref "U400") (pin "E4") (pinfunction "PX09_E4") (pintype "bidirectional+no_connect"))
    )
    (net (code "110") (name "unconnected-(U400-PX10-PadD2)") (class "Default")
      (node (ref "U400") (pin "D2") (pinfunction "PX10_D2") (pintype "bidirectional+no_connect"))
    )
    (net (code "111") (name "unconnected-(U400-PX13-PadD3)") (class "Default")
      (node (ref "U400") (pin "D3") (pinfunction "PX13_D3") (pintype "bidirectional+no_connect"))
    )
    (net (code "112") (name "unconnected-(U400-PX16_{slash}_PX53-PadD4)") (class "Default")
      (node (ref "U400") (pin "D4") (pinfunction "PX16_/_PX53_D4") (pintype "bidirectional+no_connect"))
    )
    (net (code "113") (name "unconnected-(U400-PX21-PadH2)") (class "Default")
      (node (ref "U400") (pin "H2") (pinfunction "PX21_H2") (pintype "bidirectional+no_connect"))
    )
    (net (code "114") (name "unconnected-(U400-PX23-PadK1)") (class "Default")
      (node (ref "U400") (pin "K1") (pinfunction "PX23_K1") (pintype "bidirectional+no_connect"))
    )
    (net (code "115") (name "unconnected-(U400-PX24-PadJ2)") (class "Default")
      (node (ref "U400") (pin "J2") (pinfunction "PX24_J2") (pintype "bidirectional+no_connect"))
    )
    (net (code "116") (name "unconnected-(U400-PX25-PadH4)") (class "Default")
      (node (ref "U400") (pin "H4") (pinfunction "PX25_H4") (pintype "bidirectional+no_connect"))
    )
    (net (code "117") (name "unconnected-(U400-PX31-PadH5)") (class "Default")
      (node (ref "U400") (pin "H5") (pinfunction "PX31_H5") (pintype "bidirectional+no_connect"))
    )
    (net (code "118") (name "unconnected-(XC400-Pad2)") (class "Default")
      (node (ref "XC400") (pin "2") (pinfunction "2_2") (pintype "passive+no_connect"))
    )
    (net (code "119") (name "unconnected-(XC400-Pad4)") (class "Default")
      (node (ref "XC400") (pin "4") (pinfunction "4_4") (pintype "passive+no_connect"))
    )
  )
)
